# untitled.net
KiCad netlist of a schematic drawn in EAGLE
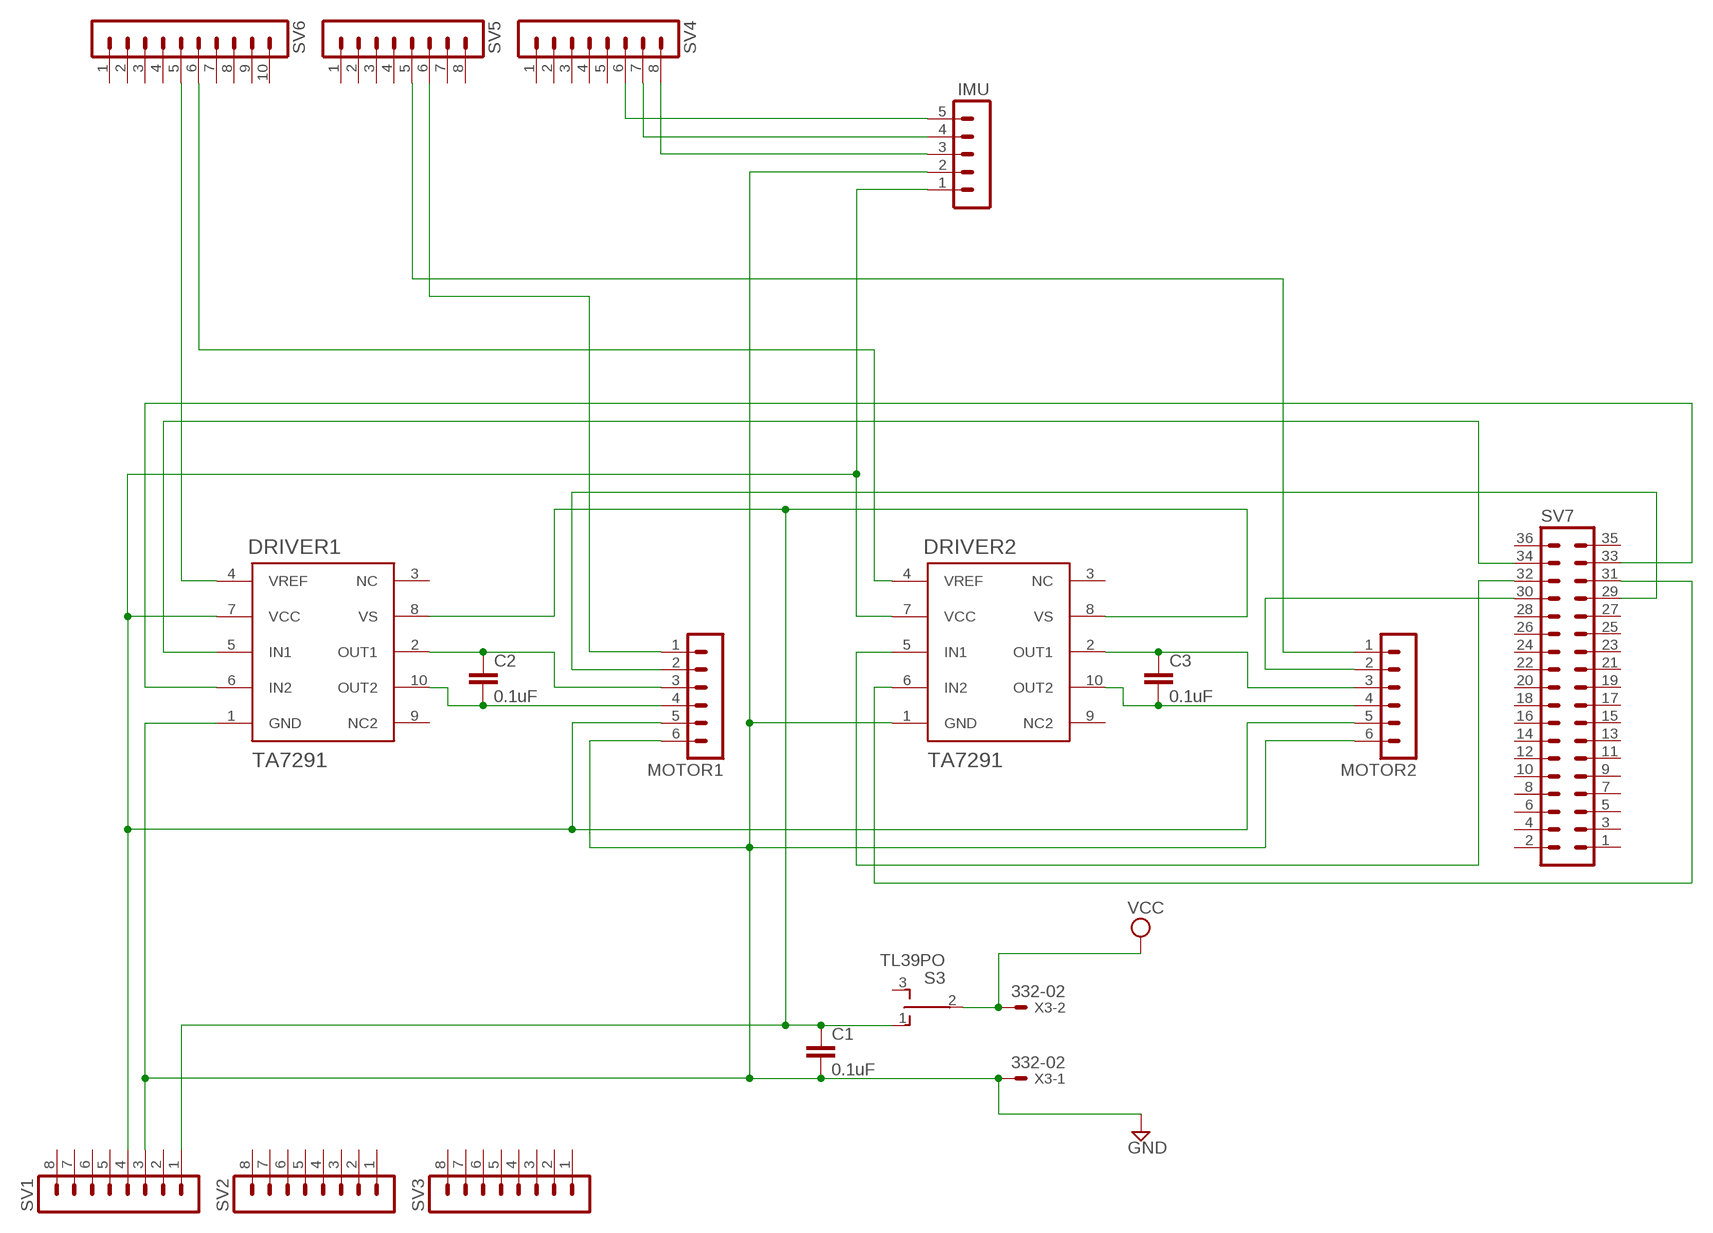
[diagram p0: schematic, sheet 1]

(export (version "E")
  (design (tool "Eeschema 10.0.6"))
  (components
    (comp (ref "C1")
      (value "0.1uF")
      (footprint "eagle-import:C5B2.5")
      (libsource (lib "eagle-import") (part "C5/2.5"))
    )
    (comp (ref "C2")
      (value "0.1uF")
      (footprint "eagle-import:C5B2.5")
      (libsource (lib "eagle-import") (part "C5/2.5"))
    )
    (comp (ref "C3")
      (value "0.1uF")
      (footprint "eagle-import:C5B2.5")
      (libsource (lib "eagle-import") (part "C5/2.5"))
    )
    (comp (ref "DRIVER1")
      (value "TA7291")
      (footprint "eagle-import:HSIP10")
      (libsource (lib "eagle-import") (part "TA7291"))
    )
    (comp (ref "DRIVER2")
      (value "TA7291")
      (footprint "eagle-import:HSIP10")
      (libsource (lib "eagle-import") (part "TA7291"))
    )
    (comp (ref "IMU")
      (value "MA05-1")
      (footprint "eagle-import:MA05-1")
      (libsource (lib "eagle-import") (part "MA05-1"))
    )
    (comp (ref "MOTOR1")
      (value "MA06-1")
      (footprint "eagle-import:MA06-1")
      (libsource (lib "eagle-import") (part "MA06-1"))
    )
    (comp (ref "MOTOR2")
      (value "MA06-1")
      (footprint "eagle-import:MA06-1")
      (libsource (lib "eagle-import") (part "MA06-1"))
    )
    (comp (ref "S3")
      (value "TL39PO")
      (footprint "eagle-import:TL3XPO")
      (libsource (lib "eagle-import") (part "TL39PO"))
    )
    (comp (ref "SV1")
      (value "MA08-1")
      (footprint "eagle-import:MA08-1")
      (libsource (lib "eagle-import") (part "MA08-1"))
    )
    (comp (ref "SV2")
      (value "MA08-1")
      (footprint "eagle-import:MA08-1")
      (libsource (lib "eagle-import") (part "MA08-1"))
    )
    (comp (ref "SV3")
      (value "MA08-1")
      (footprint "eagle-import:MA08-1")
      (libsource (lib "eagle-import") (part "MA08-1"))
    )
    (comp (ref "SV4")
      (value "MA08-1")
      (footprint "eagle-import:MA08-1")
      (libsource (lib "eagle-import") (part "MA08-1"))
    )
    (comp (ref "SV5")
      (value "MA08-1")
      (footprint "eagle-import:MA08-1")
      (libsource (lib "eagle-import") (part "MA08-1"))
    )
    (comp (ref "SV6")
      (value "MA10-1")
      (footprint "eagle-import:MA10-1")
      (libsource (lib "eagle-import") (part "MA10-1"))
    )
    (comp (ref "SV7")
      (value "MA18-2")
      (footprint "eagle-import:MA18-2")
      (libsource (lib "eagle-import") (part "MA18-2"))
    )
    (comp (ref "X3")
      (value "332-02")
      (footprint "eagle-import:332-02")
      (libsource (lib "eagle-import") (part "332-02"))
    )
  )
  (nets
    (net (code "1") (name "GND") (class "Default")
      (node (ref "C1") (pin "2") (pinfunction "2_2") (pintype "passive"))
      (node (ref "DRIVER1") (pin "1") (pinfunction "GND_1") (pintype "bidirectional"))
      (node (ref "DRIVER2") (pin "1") (pinfunction "GND_1") (pintype "bidirectional"))
      (node (ref "IMU") (pin "2") (pinfunction "2_2") (pintype "passive"))
      (node (ref "MOTOR1") (pin "6") (pinfunction "6_6") (pintype "passive"))
      (node (ref "MOTOR2") (pin "6") (pinfunction "6_6") (pintype "passive"))
      (node (ref "SV1") (pin "3") (pinfunction "3_3") (pintype "passive"))
      (node (ref "X3") (pin "1") (pinfunction "S_1") (pintype "passive"))
    )
    (net (code "2") (name "Net-(DRIVER1-IN1)") (class "Default")
      (node (ref "DRIVER1") (pin "5") (pinfunction "IN1_5") (pintype "bidirectional"))
      (node (ref "SV7") (pin "34") (pinfunction "34_34") (pintype "passive"))
    )
    (net (code "3") (name "Net-(DRIVER1-IN2)") (class "Default")
      (node (ref "DRIVER1") (pin "6") (pinfunction "IN2_6") (pintype "bidirectional"))
      (node (ref "SV7") (pin "33") (pinfunction "33_33") (pintype "passive"))
    )
    (net (code "4") (name "Net-(DRIVER1-OUT1)") (class "Default")
      (node (ref "C2") (pin "1") (pinfunction "1_1") (pintype "passive"))
      (node (ref "DRIVER1") (pin "2") (pinfunction "OUT1_2") (pintype "bidirectional"))
      (node (ref "MOTOR1") (pin "3") (pinfunction "3_3") (pintype "passive"))
    )
    (net (code "5") (name "Net-(DRIVER1-OUT2)") (class "Default")
      (node (ref "C2") (pin "2") (pinfunction "2_2") (pintype "passive"))
      (node (ref "DRIVER1") (pin "10") (pinfunction "OUT2_10") (pintype "bidirectional"))
      (node (ref "MOTOR1") (pin "4") (pinfunction "4_4") (pintype "passive"))
    )
    (net (code "6") (name "Net-(DRIVER1-VCC)") (class "Default")
      (node (ref "DRIVER1") (pin "7") (pinfunction "VCC_7") (pintype "bidirectional"))
      (node (ref "DRIVER2") (pin "7") (pinfunction "VCC_7") (pintype "bidirectional"))
      (node (ref "IMU") (pin "1") (pinfunction "1_1") (pintype "passive"))
      (node (ref "MOTOR1") (pin "5") (pinfunction "5_5") (pintype "passive"))
      (node (ref "MOTOR2") (pin "5") (pinfunction "5_5") (pintype "passive"))
      (node (ref "SV1") (pin "4") (pinfunction "4_4") (pintype "passive"))
    )
    (net (code "7") (name "Net-(DRIVER1-VREF)") (class "Default")
      (node (ref "DRIVER1") (pin "4") (pinfunction "VREF_4") (pintype "bidirectional"))
      (node (ref "SV6") (pin "5") (pinfunction "5_5") (pintype "passive"))
    )
    (net (code "8") (name "Net-(DRIVER1-VS)") (class "Default")
      (node (ref "C1") (pin "1") (pinfunction "1_1") (pintype "passive"))
      (node (ref "DRIVER1") (pin "8") (pinfunction "VS_8") (pintype "bidirectional"))
      (node (ref "DRIVER2") (pin "8") (pinfunction "VS_8") (pintype "bidirectional"))
      (node (ref "S3") (pin "1") (pinfunction "O_1") (pintype "passive"))
      (node (ref "SV1") (pin "1") (pinfunction "1_1") (pintype "passive"))
    )
    (net (code "9") (name "Net-(DRIVER2-IN1)") (class "Default")
      (node (ref "DRIVER2") (pin "5") (pinfunction "IN1_5") (pintype "bidirectional"))
      (node (ref "SV7") (pin "32") (pinfunction "32_32") (pintype "passive"))
    )
    (net (code "10") (name "Net-(DRIVER2-IN2)") (class "Default")
      (node (ref "DRIVER2") (pin "6") (pinfunction "IN2_6") (pintype "bidirectional"))
      (node (ref "SV7") (pin "31") (pinfunction "31_31") (pintype "passive"))
    )
    (net (code "11") (name "Net-(DRIVER2-OUT1)") (class "Default")
      (node (ref "C3") (pin "1") (pinfunction "1_1") (pintype "passive"))
      (node (ref "DRIVER2") (pin "2") (pinfunction "OUT1_2") (pintype "bidirectional"))
      (node (ref "MOTOR2") (pin "3") (pinfunction "3_3") (pintype "passive"))
    )
    (net (code "12") (name "Net-(DRIVER2-OUT2)") (class "Default")
      (node (ref "C3") (pin "2") (pinfunction "2_2") (pintype "passive"))
      (node (ref "DRIVER2") (pin "10") (pinfunction "OUT2_10") (pintype "bidirectional"))
      (node (ref "MOTOR2") (pin "4") (pinfunction "4_4") (pintype "passive"))
    )
    (net (code "13") (name "Net-(DRIVER2-VREF)") (class "Default")
      (node (ref "DRIVER2") (pin "4") (pinfunction "VREF_4") (pintype "bidirectional"))
      (node (ref "SV6") (pin "6") (pinfunction "6_6") (pintype "passive"))
    )
    (net (code "14") (name "Net-(IMU-Pad3)") (class "Default")
      (node (ref "IMU") (pin "3") (pinfunction "3_3") (pintype "passive"))
      (node (ref "SV4") (pin "8") (pinfunction "8_8") (pintype "passive"))
    )
    (net (code "15") (name "Net-(IMU-Pad4)") (class "Default")
      (node (ref "IMU") (pin "4") (pinfunction "4_4") (pintype "passive"))
      (node (ref "SV4") (pin "7") (pinfunction "7_7") (pintype "passive"))
    )
    (net (code "16") (name "Net-(IMU-Pad5)") (class "Default")
      (node (ref "IMU") (pin "5") (pinfunction "5_5") (pintype "passive"))
      (node (ref "SV4") (pin "6") (pinfunction "6_6") (pintype "passive"))
    )
    (net (code "17") (name "Net-(MOTOR1-Pad1)") (class "Default")
      (node (ref "MOTOR1") (pin "1") (pinfunction "1_1") (pintype "passive"))
      (node (ref "SV5") (pin "6") (pinfunction "6_6") (pintype "passive"))
    )
    (net (code "18") (name "Net-(MOTOR1-Pad2)") (class "Default")
      (node (ref "MOTOR1") (pin "2") (pinfunction "2_2") (pintype "passive"))
      (node (ref "SV7") (pin "29") (pinfunction "29_29") (pintype "passive"))
    )
    (net (code "19") (name "Net-(MOTOR2-Pad1)") (class "Default")
      (node (ref "MOTOR2") (pin "1") (pinfunction "1_1") (pintype "passive"))
      (node (ref "SV5") (pin "5") (pinfunction "5_5") (pintype "passive"))
    )
    (net (code "20") (name "Net-(MOTOR2-Pad2)") (class "Default")
      (node (ref "MOTOR2") (pin "2") (pinfunction "2_2") (pintype "passive"))
      (node (ref "SV7") (pin "30") (pinfunction "30_30") (pintype "passive"))
    )
    (net (code "21") (name "VCC") (class "Default")
      (node (ref "S3") (pin "2") (pinfunction "P_2") (pintype "passive"))
      (node (ref "X3") (pin "2") (pinfunction "S_2") (pintype "passive"))
    )
    (net (code "22") (name "unconnected-(DRIVER1-NC-Pad3)") (class "Default")
      (node (ref "DRIVER1") (pin "3") (pinfunction "NC_3") (pintype "bidirectional"))
    )
    (net (code "23") (name "unconnected-(DRIVER1-NC2-Pad9)") (class "Default")
      (node (ref "DRIVER1") (pin "9") (pinfunction "NC2_9") (pintype "bidirectional"))
    )
    (net (code "24") (name "unconnected-(DRIVER2-NC-Pad3)") (class "Default")
      (node (ref "DRIVER2") (pin "3") (pinfunction "NC_3") (pintype "bidirectional"))
    )
    (net (code "25") (name "unconnected-(DRIVER2-NC2-Pad9)") (class "Default")
      (node (ref "DRIVER2") (pin "9") (pinfunction "NC2_9") (pintype "bidirectional"))
    )
    (net (code "26") (name "unconnected-(S3-S-Pad3)") (class "Default")
      (node (ref "S3") (pin "3") (pinfunction "S_3") (pintype "passive"))
    )
    (net (code "27") (name "unconnected-(SV1-Pad2)") (class "Default")
      (node (ref "SV1") (pin "2") (pinfunction "2_2") (pintype "passive"))
    )
    (net (code "28") (name "unconnected-(SV1-Pad5)") (class "Default")
      (node (ref "SV1") (pin "5") (pinfunction "5_5") (pintype "passive"))
    )
    (net (code "29") (name "unconnected-(SV1-Pad6)") (class "Default")
      (node (ref "SV1") (pin "6") (pinfunction "6_6") (pintype "passive"))
    )
    (net (code "30") (name "unconnected-(SV1-Pad7)") (class "Default")
      (node (ref "SV1") (pin "7") (pinfunction "7_7") (pintype "passive"))
    )
    (net (code "31") (name "unconnected-(SV1-Pad8)") (class "Default")
      (node (ref "SV1") (pin "8") (pinfunction "8_8") (pintype "passive"))
    )
    (net (code "32") (name "unconnected-(SV2-Pad1)") (class "Default")
      (node (ref "SV2") (pin "1") (pinfunction "1_1") (pintype "passive"))
    )
    (net (code "33") (name "unconnected-(SV2-Pad2)") (class "Default")
      (node (ref "SV2") (pin "2") (pinfunction "2_2") (pintype "passive"))
    )
    (net (code "34") (name "unconnected-(SV2-Pad3)") (class "Default")
      (node (ref "SV2") (pin "3") (pinfunction "3_3") (pintype "passive"))
    )
    (net (code "35") (name "unconnected-(SV2-Pad4)") (class "Default")
      (node (ref "SV2") (pin "4") (pinfunction "4_4") (pintype "passive"))
    )
    (net (code "36") (name "unconnected-(SV2-Pad5)") (class "Default")
      (node (ref "SV2") (pin "5") (pinfunction "5_5") (pintype "passive"))
    )
    (net (code "37") (name "unconnected-(SV2-Pad6)") (class "Default")
      (node (ref "SV2") (pin "6") (pinfunction "6_6") (pintype "passive"))
    )
    (net (code "38") (name "unconnected-(SV2-Pad7)") (class "Default")
      (node (ref "SV2") (pin "7") (pinfunction "7_7") (pintype "passive"))
    )
    (net (code "39") (name "unconnected-(SV2-Pad8)") (class "Default")
      (node (ref "SV2") (pin "8") (pinfunction "8_8") (pintype "passive"))
    )
    (net (code "40") (name "unconnected-(SV3-Pad1)") (class "Default")
      (node (ref "SV3") (pin "1") (pinfunction "1_1") (pintype "passive"))
    )
    (net (code "41") (name "unconnected-(SV3-Pad2)") (class "Default")
      (node (ref "SV3") (pin "2") (pinfunction "2_2") (pintype "passive"))
    )
    (net (code "42") (name "unconnected-(SV3-Pad3)") (class "Default")
      (node (ref "SV3") (pin "3") (pinfunction "3_3") (pintype "passive"))
    )
    (net (code "43") (name "unconnected-(SV3-Pad4)") (class "Default")
      (node (ref "SV3") (pin "4") (pinfunction "4_4") (pintype "passive"))
    )
    (net (code "44") (name "unconnected-(SV3-Pad5)") (class "Default")
      (node (ref "SV3") (pin "5") (pinfunction "5_5") (pintype "passive"))
    )
    (net (code "45") (name "unconnected-(SV3-Pad6)") (class "Default")
      (node (ref "SV3") (pin "6") (pinfunction "6_6") (pintype "passive"))
    )
    (net (code "46") (name "unconnected-(SV3-Pad7)") (class "Default")
      (node (ref "SV3") (pin "7") (pinfunction "7_7") (pintype "passive"))
    )
    (net (code "47") (name "unconnected-(SV3-Pad8)") (class "Default")
      (node (ref "SV3") (pin "8") (pinfunction "8_8") (pintype "passive"))
    )
    (net (code "48") (name "unconnected-(SV4-Pad1)") (class "Default")
      (node (ref "SV4") (pin "1") (pinfunction "1_1") (pintype "passive"))
    )
    (net (code "49") (name "unconnected-(SV4-Pad2)") (class "Default")
      (node (ref "SV4") (pin "2") (pinfunction "2_2") (pintype "passive"))
    )
    (net (code "50") (name "unconnected-(SV4-Pad3)") (class "Default")
      (node (ref "SV4") (pin "3") (pinfunction "3_3") (pintype "passive"))
    )
    (net (code "51") (name "unconnected-(SV4-Pad4)") (class "Default")
      (node (ref "SV4") (pin "4") (pinfunction "4_4") (pintype "passive"))
    )
    (net (code "52") (name "unconnected-(SV4-Pad5)") (class "Default")
      (node (ref "SV4") (pin "5") (pinfunction "5_5") (pintype "passive"))
    )
    (net (code "53") (name "unconnected-(SV5-Pad1)") (class "Default")
      (node (ref "SV5") (pin "1") (pinfunction "1_1") (pintype "passive"))
    )
    (net (code "54") (name "unconnected-(SV5-Pad2)") (class "Default")
      (node (ref "SV5") (pin "2") (pinfunction "2_2") (pintype "passive"))
    )
    (net (code "55") (name "unconnected-(SV5-Pad3)") (class "Default")
      (node (ref "SV5") (pin "3") (pinfunction "3_3") (pintype "passive"))
    )
    (net (code "56") (name "unconnected-(SV5-Pad4)") (class "Default")
      (node (ref "SV5") (pin "4") (pinfunction "4_4") (pintype "passive"))
    )
    (net (code "57") (name "unconnected-(SV5-Pad7)") (class "Default")
      (node (ref "SV5") (pin "7") (pinfunction "7_7") (pintype "passive"))
    )
    (net (code "58") (name "unconnected-(SV5-Pad8)") (class "Default")
      (node (ref "SV5") (pin "8") (pinfunction "8_8") (pintype "passive"))
    )
    (net (code "59") (name "unconnected-(SV6-Pad1)") (class "Default")
      (node (ref "SV6") (pin "1") (pinfunction "1_1") (pintype "passive"))
    )
    (net (code "60") (name "unconnected-(SV6-Pad2)") (class "Default")
      (node (ref "SV6") (pin "2") (pinfunction "2_2") (pintype "passive"))
    )
    (net (code "61") (name "unconnected-(SV6-Pad3)") (class "Default")
      (node (ref "SV6") (pin "3") (pinfunction "3_3") (pintype "passive"))
    )
    (net (code "62") (name "unconnected-(SV6-Pad4)") (class "Default")
      (node (ref "SV6") (pin "4") (pinfunction "4_4") (pintype "passive"))
    )
    (net (code "63") (name "unconnected-(SV6-Pad7)") (class "Default")
      (node (ref "SV6") (pin "7") (pinfunction "7_7") (pintype "passive"))
    )
    (net (code "64") (name "unconnected-(SV6-Pad8)") (class "Default")
      (node (ref "SV6") (pin "8") (pinfunction "8_8") (pintype "passive"))
    )
    (net (code "65") (name "unconnected-(SV6-Pad9)") (class "Default")
      (node (ref "SV6") (pin "9") (pinfunction "9_9") (pintype "passive"))
    )
    (net (code "66") (name "unconnected-(SV6-Pad10)") (class "Default")
      (node (ref "SV6") (pin "10") (pinfunction "10_10") (pintype "passive"))
    )
    (net (code "67") (name "unconnected-(SV7-Pad1)") (class "Default")
      (node (ref "SV7") (pin "1") (pinfunction "1_1") (pintype "passive"))
    )
    (net (code "68") (name "unconnected-(SV7-Pad2)") (class "Default")
      (node (ref "SV7") (pin "2") (pinfunction "2_2") (pintype "passive"))
    )
    (net (code "69") (name "unconnected-(SV7-Pad3)") (class "Default")
      (node (ref "SV7") (pin "3") (pinfunction "3_3") (pintype "passive"))
    )
    (net (code "70") (name "unconnected-(SV7-Pad4)") (class "Default")
      (node (ref "SV7") (pin "4") (pinfunction "4_4") (pintype "passive"))
    )
    (net (code "71") (name "unconnected-(SV7-Pad5)") (class "Default")
      (node (ref "SV7") (pin "5") (pinfunction "5_5") (pintype "passive"))
    )
    (net (code "72") (name "unconnected-(SV7-Pad6)") (class "Default")
      (node (ref "SV7") (pin "6") (pinfunction "6_6") (pintype "passive"))
    )
    (net (code "73") (name "unconnected-(SV7-Pad7)") (class "Default")
      (node (ref "SV7") (pin "7") (pinfunction "7_7") (pintype "passive"))
    )
    (net (code "74") (name "unconnected-(SV7-Pad8)") (class "Default")
      (node (ref "SV7") (pin "8") (pinfunction "8_8") (pintype "passive"))
    )
    (net (code "75") (name "unconnected-(SV7-Pad9)") (class "Default")
      (node (ref "SV7") (pin "9") (pinfunction "9_9") (pintype "passive"))
    )
    (net (code "76") (name "unconnected-(SV7-Pad10)") (class "Default")
      (node (ref "SV7") (pin "10") (pinfunction "10_10") (pintype "passive"))
    )
    (net (code "77") (name "unconnected-(SV7-Pad11)") (class "Default")
      (node (ref "SV7") (pin "11") (pinfunction "11_11") (pintype "passive"))
    )
    (net (code "78") (name "unconnected-(SV7-Pad12)") (class "Default")
      (node (ref "SV7") (pin "12") (pinfunction "12_12") (pintype "passive"))
    )
    (net (code "79") (name "unconnected-(SV7-Pad13)") (class "Default")
      (node (ref "SV7") (pin "13") (pinfunction "13_13") (pintype "passive"))
    )
    (net (code "80") (name "unconnected-(SV7-Pad14)") (class "Default")
      (node (ref "SV7") (pin "14") (pinfunction "14_14") (pintype "passive"))
    )
    (net (code "81") (name "unconnected-(SV7-Pad15)") (class "Default")
      (node (ref "SV7") (pin "15") (pinfunction "15_15") (pintype "passive"))
    )
    (net (code "82") (name "unconnected-(SV7-Pad16)") (class "Default")
      (node (ref "SV7") (pin "16") (pinfunction "16_16") (pintype "passive"))
    )
    (net (code "83") (name "unconnected-(SV7-Pad17)") (class "Default")
      (node (ref "SV7") (pin "17") (pinfunction "17_17") (pintype "passive"))
    )
    (net (code "84") (name "unconnected-(SV7-Pad18)") (class "Default")
      (node (ref "SV7") (pin "18") (pinfunction "18_18") (pintype "passive"))
    )
    (net (code "85") (name "unconnected-(SV7-Pad19)") (class "Default")
      (node (ref "SV7") (pin "19") (pinfunction "19_19") (pintype "passive"))
    )
    (net (code "86") (name "unconnected-(SV7-Pad20)") (class "Default")
      (node (ref "SV7") (pin "20") (pinfunction "20_20") (pintype "passive"))
    )
    (net (code "87") (name "unconnected-(SV7-Pad21)") (class "Default")
      (node (ref "SV7") (pin "21") (pinfunction "21_21") (pintype "passive"))
    )
    (net (code "88") (name "unconnected-(SV7-Pad22)") (class "Default")
      (node (ref "SV7") (pin "22") (pinfunction "22_22") (pintype "passive"))
    )
    (net (code "89") (name "unconnected-(SV7-Pad23)") (class "Default")
      (node (ref "SV7") (pin "23") (pinfunction "23_23") (pintype "passive"))
    )
    (net (code "90") (name "unconnected-(SV7-Pad24)") (class "Default")
      (node (ref "SV7") (pin "24") (pinfunction "24_24") (pintype "passive"))
    )
    (net (code "91") (name "unconnected-(SV7-Pad25)") (class "Default")
      (node (ref "SV7") (pin "25") (pinfunction "25_25") (pintype "passive"))
    )
    (net (code "92") (name "unconnected-(SV7-Pad26)") (class "Default")
      (node (ref "SV7") (pin "26") (pinfunction "26_26") (pintype "passive"))
    )
    (net (code "93") (name "unconnected-(SV7-Pad27)") (class "Default")
      (node (ref "SV7") (pin "27") (pinfunction "27_27") (pintype "passive"))
    )
    (net (code "94") (name "unconnected-(SV7-Pad28)") (class "Default")
      (node (ref "SV7") (pin "28") (pinfunction "28_28") (pintype "passive"))
    )
    (net (code "95") (name "unconnected-(SV7-Pad35)") (class "Default")
      (node (ref "SV7") (pin "35") (pinfunction "35_35") (pintype "passive"))
    )
    (net (code "96") (name "unconnected-(SV7-Pad36)") (class "Default")
      (node (ref "SV7") (pin "36") (pinfunction "36_36") (pintype "passive"))
    )
  )
)
